# input_filter.net
KiCad netlist of a schematic drawn in Altium Designer
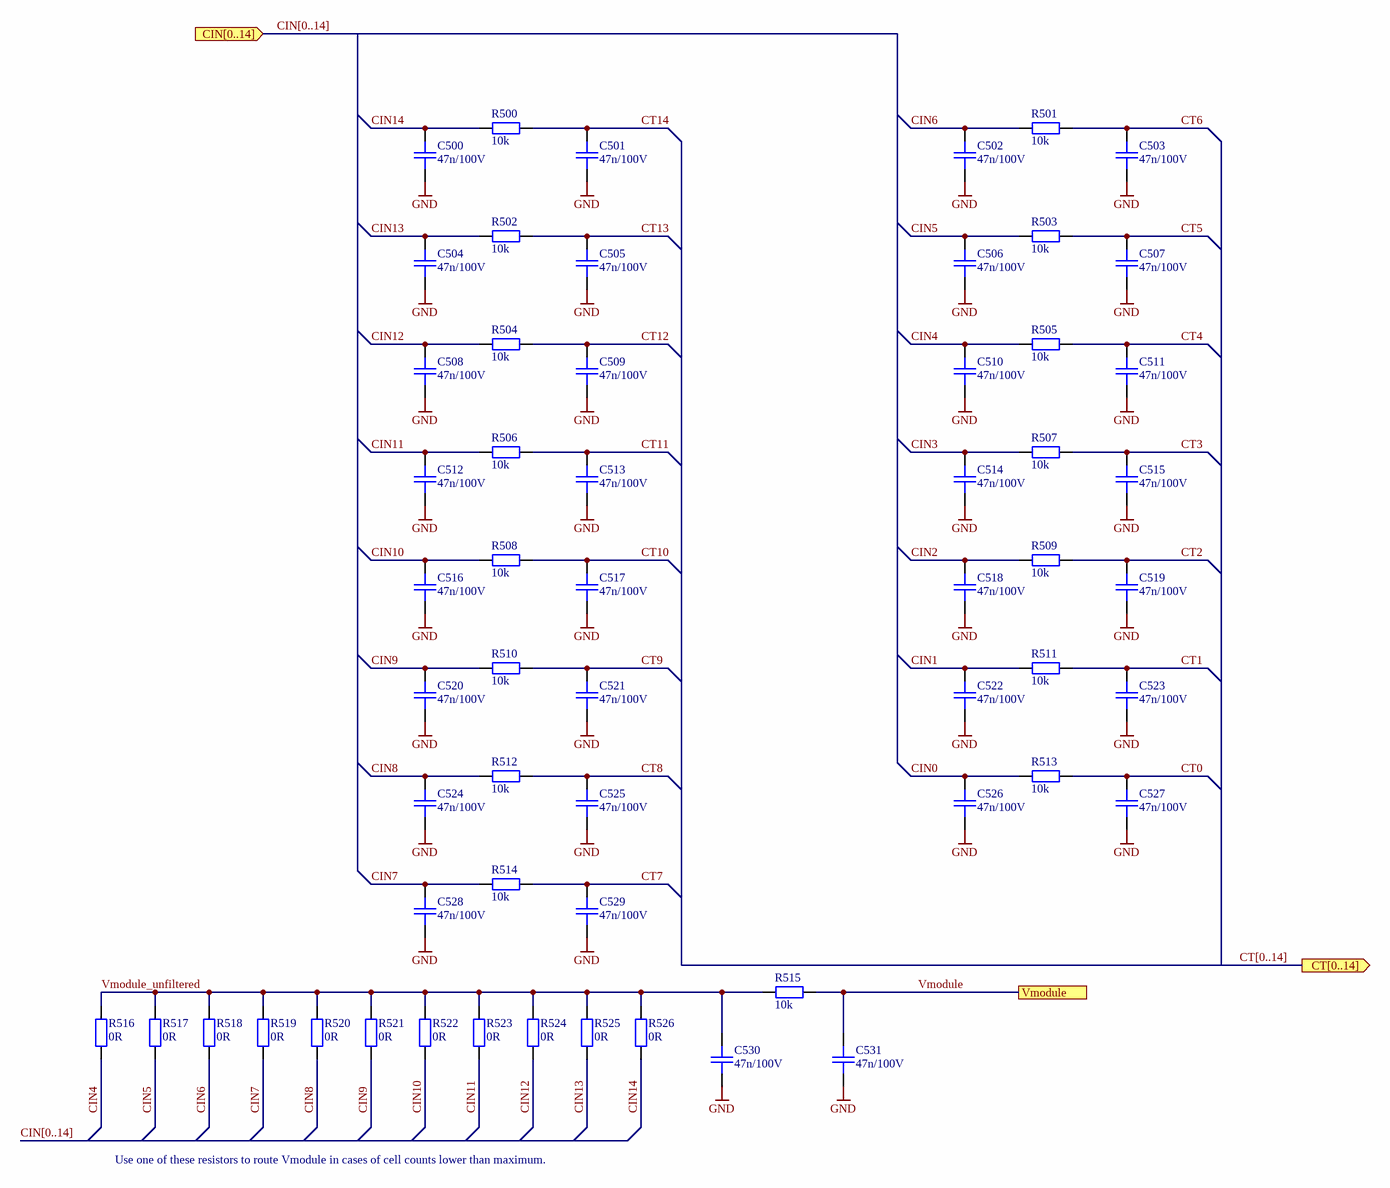
[diagram p0: input_filter.SchDoc]

(export (version "E")
  (design (tool "Eeschema 10.0.6"))
  (components
    (comp (ref "C500")
      (value "47n/100V")
      (footprint "CAPC1608X08N")
      (description "MLCC")
      (fields (field (name "PART NUMBER") "gen_C_ceramic_47n_100V_X7R_0603"))
      (libsource (lib "OE750") (part "C"))
    )
    (comp (ref "C501")
      (value "47n/100V")
      (footprint "CAPC1608X08N")
      (description "MLCC")
      (fields (field (name "PART NUMBER") "gen_C_ceramic_47n_100V_X7R_0603"))
      (libsource (lib "OE750") (part "C"))
    )
    (comp (ref "C502")
      (value "47n/100V")
      (footprint "CAPC1608X08N")
      (description "MLCC")
      (fields (field (name "PART NUMBER") "gen_C_ceramic_47n_100V_X7R_0603"))
      (libsource (lib "OE750") (part "C"))
    )
    (comp (ref "C503")
      (value "47n/100V")
      (footprint "CAPC1608X08N")
      (description "MLCC")
      (fields (field (name "PART NUMBER") "gen_C_ceramic_47n_100V_X7R_0603"))
      (libsource (lib "OE750") (part "C"))
    )
    (comp (ref "C504")
      (value "47n/100V")
      (footprint "CAPC1608X08N")
      (description "MLCC")
      (fields (field (name "PART NUMBER") "gen_C_ceramic_47n_100V_X7R_0603"))
      (libsource (lib "OE750") (part "C"))
    )
    (comp (ref "C505")
      (value "47n/100V")
      (footprint "CAPC1608X08N")
      (description "MLCC")
      (fields (field (name "PART NUMBER") "gen_C_ceramic_47n_100V_X7R_0603"))
      (libsource (lib "OE750") (part "C"))
    )
    (comp (ref "C506")
      (value "47n/100V")
      (footprint "CAPC1608X08N")
      (description "MLCC")
      (fields (field (name "PART NUMBER") "gen_C_ceramic_47n_100V_X7R_0603"))
      (libsource (lib "OE750") (part "C"))
    )
    (comp (ref "C507")
      (value "47n/100V")
      (footprint "CAPC1608X08N")
      (description "MLCC")
      (fields (field (name "PART NUMBER") "gen_C_ceramic_47n_100V_X7R_0603"))
      (libsource (lib "OE750") (part "C"))
    )
    (comp (ref "C508")
      (value "47n/100V")
      (footprint "CAPC1608X08N")
      (description "MLCC")
      (fields (field (name "PART NUMBER") "gen_C_ceramic_47n_100V_X7R_0603"))
      (libsource (lib "OE750") (part "C"))
    )
    (comp (ref "C509")
      (value "47n/100V")
      (footprint "CAPC1608X08N")
      (description "MLCC")
      (fields (field (name "PART NUMBER") "gen_C_ceramic_47n_100V_X7R_0603"))
      (libsource (lib "OE750") (part "C"))
    )
    (comp (ref "C510")
      (value "47n/100V")
      (footprint "CAPC1608X08N")
      (description "MLCC")
      (fields (field (name "PART NUMBER") "gen_C_ceramic_47n_100V_X7R_0603"))
      (libsource (lib "OE750") (part "C"))
    )
    (comp (ref "C511")
      (value "47n/100V")
      (footprint "CAPC1608X08N")
      (description "MLCC")
      (fields (field (name "PART NUMBER") "gen_C_ceramic_47n_100V_X7R_0603"))
      (libsource (lib "OE750") (part "C"))
    )
    (comp (ref "C512")
      (value "47n/100V")
      (footprint "CAPC1608X08N")
      (description "MLCC")
      (fields (field (name "PART NUMBER") "gen_C_ceramic_47n_100V_X7R_0603"))
      (libsource (lib "OE750") (part "C"))
    )
    (comp (ref "C513")
      (value "47n/100V")
      (footprint "CAPC1608X08N")
      (description "MLCC")
      (fields (field (name "PART NUMBER") "gen_C_ceramic_47n_100V_X7R_0603"))
      (libsource (lib "OE750") (part "C"))
    )
    (comp (ref "C514")
      (value "47n/100V")
      (footprint "CAPC1608X08N")
      (description "MLCC")
      (fields (field (name "PART NUMBER") "gen_C_ceramic_47n_100V_X7R_0603"))
      (libsource (lib "OE750") (part "C"))
    )
    (comp (ref "C515")
      (value "47n/100V")
      (footprint "CAPC1608X08N")
      (description "MLCC")
      (fields (field (name "PART NUMBER") "gen_C_ceramic_47n_100V_X7R_0603"))
      (libsource (lib "OE750") (part "C"))
    )
    (comp (ref "C516")
      (value "47n/100V")
      (footprint "CAPC1608X08N")
      (description "MLCC")
      (fields (field (name "PART NUMBER") "gen_C_ceramic_47n_100V_X7R_0603"))
      (libsource (lib "OE750") (part "C"))
    )
    (comp (ref "C517")
      (value "47n/100V")
      (footprint "CAPC1608X08N")
      (description "MLCC")
      (fields (field (name "PART NUMBER") "gen_C_ceramic_47n_100V_X7R_0603"))
      (libsource (lib "OE750") (part "C"))
    )
    (comp (ref "C518")
      (value "47n/100V")
      (footprint "CAPC1608X08N")
      (description "MLCC")
      (fields (field (name "PART NUMBER") "gen_C_ceramic_47n_100V_X7R_0603"))
      (libsource (lib "OE750") (part "C"))
    )
    (comp (ref "C519")
      (value "47n/100V")
      (footprint "CAPC1608X08N")
      (description "MLCC")
      (fields (field (name "PART NUMBER") "gen_C_ceramic_47n_100V_X7R_0603"))
      (libsource (lib "OE750") (part "C"))
    )
    (comp (ref "C520")
      (value "47n/100V")
      (footprint "CAPC1608X08N")
      (description "MLCC")
      (fields (field (name "PART NUMBER") "gen_C_ceramic_47n_100V_X7R_0603"))
      (libsource (lib "OE750") (part "C"))
    )
    (comp (ref "C521")
      (value "47n/100V")
      (footprint "CAPC1608X08N")
      (description "MLCC")
      (fields (field (name "PART NUMBER") "gen_C_ceramic_47n_100V_X7R_0603"))
      (libsource (lib "OE750") (part "C"))
    )
    (comp (ref "C522")
      (value "47n/100V")
      (footprint "CAPC1608X08N")
      (description "MLCC")
      (fields (field (name "PART NUMBER") "gen_C_ceramic_47n_100V_X7R_0603"))
      (libsource (lib "OE750") (part "C"))
    )
    (comp (ref "C523")
      (value "47n/100V")
      (footprint "CAPC1608X08N")
      (description "MLCC")
      (fields (field (name "PART NUMBER") "gen_C_ceramic_47n_100V_X7R_0603"))
      (libsource (lib "OE750") (part "C"))
    )
    (comp (ref "C524")
      (value "47n/100V")
      (footprint "CAPC1608X08N")
      (description "MLCC")
      (fields (field (name "PART NUMBER") "gen_C_ceramic_47n_100V_X7R_0603"))
      (libsource (lib "OE750") (part "C"))
    )
    (comp (ref "C525")
      (value "47n/100V")
      (footprint "CAPC1608X08N")
      (description "MLCC")
      (fields (field (name "PART NUMBER") "gen_C_ceramic_47n_100V_X7R_0603"))
      (libsource (lib "OE750") (part "C"))
    )
    (comp (ref "C526")
      (value "47n/100V")
      (footprint "CAPC1608X08N")
      (description "MLCC")
      (fields (field (name "PART NUMBER") "gen_C_ceramic_47n_100V_X7R_0603"))
      (libsource (lib "OE750") (part "C"))
    )
    (comp (ref "C527")
      (value "47n/100V")
      (footprint "CAPC1608X08N")
      (description "MLCC")
      (fields (field (name "PART NUMBER") "gen_C_ceramic_47n_100V_X7R_0603"))
      (libsource (lib "OE750") (part "C"))
    )
    (comp (ref "C528")
      (value "47n/100V")
      (footprint "CAPC1608X08N")
      (description "MLCC")
      (fields (field (name "PART NUMBER") "gen_C_ceramic_47n_100V_X7R_0603"))
      (libsource (lib "OE750") (part "C"))
    )
    (comp (ref "C529")
      (value "47n/100V")
      (footprint "CAPC1608X08N")
      (description "MLCC")
      (fields (field (name "PART NUMBER") "gen_C_ceramic_47n_100V_X7R_0603"))
      (libsource (lib "OE750") (part "C"))
    )
    (comp (ref "C530")
      (value "47n/100V")
      (footprint "CAPC1608X08N")
      (description "MLCC")
      (fields (field (name "PART NUMBER") "gen_C_ceramic_47n_100V_X7R_0603"))
      (libsource (lib "OE750") (part "C"))
    )
    (comp (ref "C531")
      (value "47n/100V")
      (footprint "CAPC1608X08N")
      (description "MLCC")
      (fields (field (name "PART NUMBER") "gen_C_ceramic_47n_100V_X7R_0603"))
      (libsource (lib "OE750") (part "C"))
    )
    (comp (ref "R500")
      (value "10k")
      (footprint "RESC1608X05N")
      (description "SMD Resistor 10k 0603")
      (fields (field (name "PART NUMBER") "gen_R_10k_0603") (field (name "TOLERANCE") "1%"))
      (libsource (lib "OE750") (part "R"))
    )
    (comp (ref "R501")
      (value "10k")
      (footprint "RESC1608X05N")
      (description "SMD Resistor 10k 0603")
      (fields (field (name "PART NUMBER") "gen_R_10k_0603") (field (name "TOLERANCE") "1%"))
      (libsource (lib "OE750") (part "R"))
    )
    (comp (ref "R502")
      (value "10k")
      (footprint "RESC1608X05N")
      (description "SMD Resistor 10k 0603")
      (fields (field (name "PART NUMBER") "gen_R_10k_0603") (field (name "TOLERANCE") "1%"))
      (libsource (lib "OE750") (part "R"))
    )
    (comp (ref "R503")
      (value "10k")
      (footprint "RESC1608X05N")
      (description "SMD Resistor 10k 0603")
      (fields (field (name "PART NUMBER") "gen_R_10k_0603") (field (name "TOLERANCE") "1%"))
      (libsource (lib "OE750") (part "R"))
    )
    (comp (ref "R504")
      (value "10k")
      (footprint "RESC1608X05N")
      (description "SMD Resistor 10k 0603")
      (fields (field (name "PART NUMBER") "gen_R_10k_0603") (field (name "TOLERANCE") "1%"))
      (libsource (lib "OE750") (part "R"))
    )
    (comp (ref "R505")
      (value "10k")
      (footprint "RESC1608X05N")
      (description "SMD Resistor 10k 0603")
      (fields (field (name "PART NUMBER") "gen_R_10k_0603") (field (name "TOLERANCE") "1%"))
      (libsource (lib "OE750") (part "R"))
    )
    (comp (ref "R506")
      (value "10k")
      (footprint "RESC1608X05N")
      (description "SMD Resistor 10k 0603")
      (fields (field (name "PART NUMBER") "gen_R_10k_0603") (field (name "TOLERANCE") "1%"))
      (libsource (lib "OE750") (part "R"))
    )
    (comp (ref "R507")
      (value "10k")
      (footprint "RESC1608X05N")
      (description "SMD Resistor 10k 0603")
      (fields (field (name "PART NUMBER") "gen_R_10k_0603") (field (name "TOLERANCE") "1%"))
      (libsource (lib "OE750") (part "R"))
    )
    (comp (ref "R508")
      (value "10k")
      (footprint "RESC1608X05N")
      (description "SMD Resistor 10k 0603")
      (fields (field (name "PART NUMBER") "gen_R_10k_0603") (field (name "TOLERANCE") "1%"))
      (libsource (lib "OE750") (part "R"))
    )
    (comp (ref "R509")
      (value "10k")
      (footprint "RESC1608X05N")
      (description "SMD Resistor 10k 0603")
      (fields (field (name "PART NUMBER") "gen_R_10k_0603") (field (name "TOLERANCE") "1%"))
      (libsource (lib "OE750") (part "R"))
    )
    (comp (ref "R510")
      (value "10k")
      (footprint "RESC1608X05N")
      (description "SMD Resistor 10k 0603")
      (fields (field (name "PART NUMBER") "gen_R_10k_0603") (field (name "TOLERANCE") "1%"))
      (libsource (lib "OE750") (part "R"))
    )
    (comp (ref "R511")
      (value "10k")
      (footprint "RESC1608X05N")
      (description "SMD Resistor 10k 0603")
      (fields (field (name "PART NUMBER") "gen_R_10k_0603") (field (name "TOLERANCE") "1%"))
      (libsource (lib "OE750") (part "R"))
    )
    (comp (ref "R512")
      (value "10k")
      (footprint "RESC1608X05N")
      (description "SMD Resistor 10k 0603")
      (fields (field (name "PART NUMBER") "gen_R_10k_0603") (field (name "TOLERANCE") "1%"))
      (libsource (lib "OE750") (part "R"))
    )
    (comp (ref "R513")
      (value "10k")
      (footprint "RESC1608X05N")
      (description "SMD Resistor 10k 0603")
      (fields (field (name "PART NUMBER") "gen_R_10k_0603") (field (name "TOLERANCE") "1%"))
      (libsource (lib "OE750") (part "R"))
    )
    (comp (ref "R514")
      (value "10k")
      (footprint "RESC1608X05N")
      (description "SMD Resistor 10k 0603")
      (fields (field (name "PART NUMBER") "gen_R_10k_0603") (field (name "TOLERANCE") "1%"))
      (libsource (lib "OE750") (part "R"))
    )
    (comp (ref "R515")
      (value "10k")
      (footprint "RESC1608X05N")
      (description "SMD Resistor 10k 0603")
      (fields (field (name "PART NUMBER") "gen_R_10k_0603") (field (name "TOLERANCE") "1%"))
      (libsource (lib "OE750") (part "R"))
    )
    (comp (ref "R516")
      (value "0R")
      (footprint "RESC1608X05N")
      (description "SMD Resistor 0R 0603")
      (fields (field (name "PART NUMBER") "gen_R_0R_0603") (field (name "POWER") "0.1W"))
      (libsource (lib "OE750") (part "R"))
    )
    (comp (ref "R517")
      (value "0R")
      (footprint "RESC1608X05N")
      (description "SMD Resistor 0R 0603")
      (fields (field (name "PART NUMBER") "gen_R_0R_0603") (field (name "POWER") "0.1W"))
      (libsource (lib "OE750") (part "R"))
    )
    (comp (ref "R518")
      (value "0R")
      (footprint "RESC1608X05N")
      (description "SMD Resistor 0R 0603")
      (fields (field (name "PART NUMBER") "gen_R_0R_0603") (field (name "POWER") "0.1W"))
      (libsource (lib "OE750") (part "R"))
    )
    (comp (ref "R519")
      (value "0R")
      (footprint "RESC1608X05N")
      (description "SMD Resistor 0R 0603")
      (fields (field (name "PART NUMBER") "gen_R_0R_0603") (field (name "POWER") "0.1W"))
      (libsource (lib "OE750") (part "R"))
    )
    (comp (ref "R520")
      (value "0R")
      (footprint "RESC1608X05N")
      (description "SMD Resistor 0R 0603")
      (fields (field (name "PART NUMBER") "gen_R_0R_0603") (field (name "POWER") "0.1W"))
      (libsource (lib "OE750") (part "R"))
    )
    (comp (ref "R521")
      (value "0R")
      (footprint "RESC1608X05N")
      (description "SMD Resistor 0R 0603")
      (fields (field (name "PART NUMBER") "gen_R_0R_0603") (field (name "POWER") "0.1W"))
      (libsource (lib "OE750") (part "R"))
    )
    (comp (ref "R522")
      (value "0R")
      (footprint "RESC1608X05N")
      (description "SMD Resistor 0R 0603")
      (fields (field (name "PART NUMBER") "gen_R_0R_0603") (field (name "POWER") "0.1W"))
      (libsource (lib "OE750") (part "R"))
    )
    (comp (ref "R523")
      (value "0R")
      (footprint "RESC1608X05N")
      (description "SMD Resistor 0R 0603")
      (fields (field (name "PART NUMBER") "gen_R_0R_0603") (field (name "POWER") "0.1W"))
      (libsource (lib "OE750") (part "R"))
    )
    (comp (ref "R524")
      (value "0R")
      (footprint "RESC1608X05N")
      (description "SMD Resistor 0R 0603")
      (fields (field (name "PART NUMBER") "gen_R_0R_0603") (field (name "POWER") "0.1W"))
      (libsource (lib "OE750") (part "R"))
    )
    (comp (ref "R525")
      (value "0R")
      (footprint "RESC1608X05N")
      (description "SMD Resistor 0R 0603")
      (fields (field (name "PART NUMBER") "gen_R_0R_0603") (field (name "POWER") "0.1W"))
      (libsource (lib "OE750") (part "R"))
    )
    (comp (ref "R526")
      (value "0R")
      (footprint "RESC1608X05N")
      (description "SMD Resistor 0R 0603")
      (fields (field (name "PART NUMBER") "gen_R_0R_0603") (field (name "POWER") "0.1W"))
      (libsource (lib "OE750") (part "R"))
    )
  )
  (nets
    (net (code "1") (name "/CIN0") (class "Default")
      (node (ref "C526") (pin "2") (pinfunction "2_2") (pintype "passive"))
      (node (ref "R513") (pin "2") (pinfunction "2_2") (pintype "passive"))
    )
    (net (code "2") (name "/CIN1") (class "Default")
      (node (ref "C522") (pin "2") (pinfunction "2_2") (pintype "passive"))
      (node (ref "R511") (pin "2") (pinfunction "2_2") (pintype "passive"))
    )
    (net (code "3") (name "/CIN2") (class "Default")
      (node (ref "C518") (pin "2") (pinfunction "2_2") (pintype "passive"))
      (node (ref "R509") (pin "2") (pinfunction "2_2") (pintype "passive"))
    )
    (net (code "4") (name "/CIN3") (class "Default")
      (node (ref "C514") (pin "2") (pinfunction "2_2") (pintype "passive"))
      (node (ref "R507") (pin "2") (pinfunction "2_2") (pintype "passive"))
    )
    (net (code "5") (name "/CIN4") (class "Default")
      (node (ref "C510") (pin "2") (pinfunction "2_2") (pintype "passive"))
      (node (ref "R505") (pin "2") (pinfunction "2_2") (pintype "passive"))
      (node (ref "R516") (pin "1") (pinfunction "1_1") (pintype "passive"))
    )
    (net (code "6") (name "/CIN5") (class "Default")
      (node (ref "C506") (pin "2") (pinfunction "2_2") (pintype "passive"))
      (node (ref "R503") (pin "2") (pinfunction "2_2") (pintype "passive"))
      (node (ref "R517") (pin "1") (pinfunction "1_1") (pintype "passive"))
    )
    (net (code "7") (name "/CIN6") (class "Default")
      (node (ref "C502") (pin "2") (pinfunction "2_2") (pintype "passive"))
      (node (ref "R501") (pin "2") (pinfunction "2_2") (pintype "passive"))
      (node (ref "R518") (pin "1") (pinfunction "1_1") (pintype "passive"))
    )
    (net (code "8") (name "/CIN7") (class "Default")
      (node (ref "C528") (pin "2") (pinfunction "2_2") (pintype "passive"))
      (node (ref "R514") (pin "2") (pinfunction "2_2") (pintype "passive"))
      (node (ref "R519") (pin "1") (pinfunction "1_1") (pintype "passive"))
    )
    (net (code "9") (name "/CIN8") (class "Default")
      (node (ref "C524") (pin "2") (pinfunction "2_2") (pintype "passive"))
      (node (ref "R512") (pin "2") (pinfunction "2_2") (pintype "passive"))
      (node (ref "R520") (pin "1") (pinfunction "1_1") (pintype "passive"))
    )
    (net (code "10") (name "/CIN9") (class "Default")
      (node (ref "C520") (pin "2") (pinfunction "2_2") (pintype "passive"))
      (node (ref "R510") (pin "2") (pinfunction "2_2") (pintype "passive"))
      (node (ref "R521") (pin "1") (pinfunction "1_1") (pintype "passive"))
    )
    (net (code "11") (name "/CIN10") (class "Default")
      (node (ref "C516") (pin "2") (pinfunction "2_2") (pintype "passive"))
      (node (ref "R508") (pin "2") (pinfunction "2_2") (pintype "passive"))
      (node (ref "R522") (pin "1") (pinfunction "1_1") (pintype "passive"))
    )
    (net (code "12") (name "/CIN11") (class "Default")
      (node (ref "C512") (pin "2") (pinfunction "2_2") (pintype "passive"))
      (node (ref "R506") (pin "2") (pinfunction "2_2") (pintype "passive"))
      (node (ref "R523") (pin "1") (pinfunction "1_1") (pintype "passive"))
    )
    (net (code "13") (name "/CIN12") (class "Default")
      (node (ref "C508") (pin "2") (pinfunction "2_2") (pintype "passive"))
      (node (ref "R504") (pin "2") (pinfunction "2_2") (pintype "passive"))
      (node (ref "R524") (pin "1") (pinfunction "1_1") (pintype "passive"))
    )
    (net (code "14") (name "/CIN13") (class "Default")
      (node (ref "C504") (pin "2") (pinfunction "2_2") (pintype "passive"))
      (node (ref "R502") (pin "2") (pinfunction "2_2") (pintype "passive"))
      (node (ref "R525") (pin "1") (pinfunction "1_1") (pintype "passive"))
    )
    (net (code "15") (name "/CIN14") (class "Default")
      (node (ref "C500") (pin "2") (pinfunction "2_2") (pintype "passive"))
      (node (ref "R500") (pin "2") (pinfunction "2_2") (pintype "passive"))
      (node (ref "R526") (pin "1") (pinfunction "1_1") (pintype "passive"))
    )
    (net (code "17") (name "/CT0") (class "Default")
      (node (ref "C527") (pin "2") (pinfunction "2_2") (pintype "passive"))
      (node (ref "R513") (pin "1") (pinfunction "1_1") (pintype "passive"))
    )
    (net (code "18") (name "/CT1") (class "Default")
      (node (ref "C523") (pin "2") (pinfunction "2_2") (pintype "passive"))
      (node (ref "R511") (pin "1") (pinfunction "1_1") (pintype "passive"))
    )
    (net (code "19") (name "/CT2") (class "Default")
      (node (ref "C519") (pin "2") (pinfunction "2_2") (pintype "passive"))
      (node (ref "R509") (pin "1") (pinfunction "1_1") (pintype "passive"))
    )
    (net (code "20") (name "/CT3") (class "Default")
      (node (ref "C515") (pin "2") (pinfunction "2_2") (pintype "passive"))
      (node (ref "R507") (pin "1") (pinfunction "1_1") (pintype "passive"))
    )
    (net (code "21") (name "/CT4") (class "Default")
      (node (ref "C511") (pin "2") (pinfunction "2_2") (pintype "passive"))
      (node (ref "R505") (pin "1") (pinfunction "1_1") (pintype "passive"))
    )
    (net (code "22") (name "/CT5") (class "Default")
      (node (ref "C507") (pin "2") (pinfunction "2_2") (pintype "passive"))
      (node (ref "R503") (pin "1") (pinfunction "1_1") (pintype "passive"))
    )
    (net (code "23") (name "/CT6") (class "Default")
      (node (ref "C503") (pin "2") (pinfunction "2_2") (pintype "passive"))
      (node (ref "R501") (pin "1") (pinfunction "1_1") (pintype "passive"))
    )
    (net (code "24") (name "/CT7") (class "Default")
      (node (ref "C529") (pin "2") (pinfunction "2_2") (pintype "passive"))
      (node (ref "R514") (pin "1") (pinfunction "1_1") (pintype "passive"))
    )
    (net (code "25") (name "/CT8") (class "Default")
      (node (ref "C525") (pin "2") (pinfunction "2_2") (pintype "passive"))
      (node (ref "R512") (pin "1") (pinfunction "1_1") (pintype "passive"))
    )
    (net (code "26") (name "/CT9") (class "Default")
      (node (ref "C521") (pin "2") (pinfunction "2_2") (pintype "passive"))
      (node (ref "R510") (pin "1") (pinfunction "1_1") (pintype "passive"))
    )
    (net (code "27") (name "/CT10") (class "Default")
      (node (ref "C517") (pin "2") (pinfunction "2_2") (pintype "passive"))
      (node (ref "R508") (pin "1") (pinfunction "1_1") (pintype "passive"))
    )
    (net (code "28") (name "/CT11") (class "Default")
      (node (ref "C513") (pin "2") (pinfunction "2_2") (pintype "passive"))
      (node (ref "R506") (pin "1") (pinfunction "1_1") (pintype "passive"))
    )
    (net (code "29") (name "/CT12") (class "Default")
      (node (ref "C509") (pin "2") (pinfunction "2_2") (pintype "passive"))
      (node (ref "R504") (pin "1") (pinfunction "1_1") (pintype "passive"))
    )
    (net (code "30") (name "/CT13") (class "Default")
      (node (ref "C505") (pin "2") (pinfunction "2_2") (pintype "passive"))
      (node (ref "R502") (pin "1") (pinfunction "1_1") (pintype "passive"))
    )
    (net (code "31") (name "/CT14") (class "Default")
      (node (ref "C501") (pin "2") (pinfunction "2_2") (pintype "passive"))
      (node (ref "R500") (pin "1") (pinfunction "1_1") (pintype "passive"))
    )
    (net (code "33") (name "/Vmodule") (class "Default")
      (node (ref "C531") (pin "2") (pinfunction "2_2") (pintype "passive"))
      (node (ref "R515") (pin "1") (pinfunction "1_1") (pintype "passive"))
    )
    (net (code "34") (name "/Vmodule_unfiltered") (class "Default")
      (node (ref "C530") (pin "2") (pinfunction "2_2") (pintype "passive"))
      (node (ref "R515") (pin "2") (pinfunction "2_2") (pintype "passive"))
      (node (ref "R516") (pin "2") (pinfunction "2_2") (pintype "passive"))
      (node (ref "R517") (pin "2") (pinfunction "2_2") (pintype "passive"))
      (node (ref "R518") (pin "2") (pinfunction "2_2") (pintype "passive"))
      (node (ref "R519") (pin "2") (pinfunction "2_2") (pintype "passive"))
      (node (ref "R520") (pin "2") (pinfunction "2_2") (pintype "passive"))
      (node (ref "R521") (pin "2") (pinfunction "2_2") (pintype "passive"))
      (node (ref "R522") (pin "2") (pinfunction "2_2") (pintype "passive"))
      (node (ref "R523") (pin "2") (pinfunction "2_2") (pintype "passive"))
      (node (ref "R524") (pin "2") (pinfunction "2_2") (pintype "passive"))
      (node (ref "R525") (pin "2") (pinfunction "2_2") (pintype "passive"))
      (node (ref "R526") (pin "2") (pinfunction "2_2") (pintype "passive"))
    )
    (net (code "35") (name "GND") (class "Default")
      (node (ref "C500") (pin "1") (pinfunction "1_1") (pintype "passive"))
      (node (ref "C501") (pin "1") (pinfunction "1_1") (pintype "passive"))
      (node (ref "C502") (pin "1") (pinfunction "1_1") (pintype "passive"))
      (node (ref "C503") (pin "1") (pinfunction "1_1") (pintype "passive"))
      (node (ref "C504") (pin "1") (pinfunction "1_1") (pintype "passive"))
      (node (ref "C505") (pin "1") (pinfunction "1_1") (pintype "passive"))
      (node (ref "C506") (pin "1") (pinfunction "1_1") (pintype "passive"))
      (node (ref "C507") (pin "1") (pinfunction "1_1") (pintype "passive"))
      (node (ref "C508") (pin "1") (pinfunction "1_1") (pintype "passive"))
      (node (ref "C509") (pin "1") (pinfunction "1_1") (pintype "passive"))
      (node (ref "C510") (pin "1") (pinfunction "1_1") (pintype "passive"))
      (node (ref "C511") (pin "1") (pinfunction "1_1") (pintype "passive"))
      (node (ref "C512") (pin "1") (pinfunction "1_1") (pintype "passive"))
      (node (ref "C513") (pin "1") (pinfunction "1_1") (pintype "passive"))
      (node (ref "C514") (pin "1") (pinfunction "1_1") (pintype "passive"))
      (node (ref "C515") (pin "1") (pinfunction "1_1") (pintype "passive"))
      (node (ref "C516") (pin "1") (pinfunction "1_1") (pintype "passive"))
      (node (ref "C517") (pin "1") (pinfunction "1_1") (pintype "passive"))
      (node (ref "C518") (pin "1") (pinfunction "1_1") (pintype "passive"))
      (node (ref "C519") (pin "1") (pinfunction "1_1") (pintype "passive"))
      (node (ref "C520") (pin "1") (pinfunction "1_1") (pintype "passive"))
      (node (ref "C521") (pin "1") (pinfunction "1_1") (pintype "passive"))
      (node (ref "C522") (pin "1") (pinfunction "1_1") (pintype "passive"))
      (node (ref "C523") (pin "1") (pinfunction "1_1") (pintype "passive"))
      (node (ref "C524") (pin "1") (pinfunction "1_1") (pintype "passive"))
      (node (ref "C525") (pin "1") (pinfunction "1_1") (pintype "passive"))
      (node (ref "C526") (pin "1") (pinfunction "1_1") (pintype "passive"))
      (node (ref "C527") (pin "1") (pinfunction "1_1") (pintype "passive"))
      (node (ref "C528") (pin "1") (pinfunction "1_1") (pintype "passive"))
      (node (ref "C529") (pin "1") (pinfunction "1_1") (pintype "passive"))
      (node (ref "C530") (pin "1") (pinfunction "1_1") (pintype "passive"))
      (node (ref "C531") (pin "1") (pinfunction "1_1") (pintype "passive"))
    )
  )
)
